# uSD.net
KiCad netlist of a schematic drawn in Altium Designer
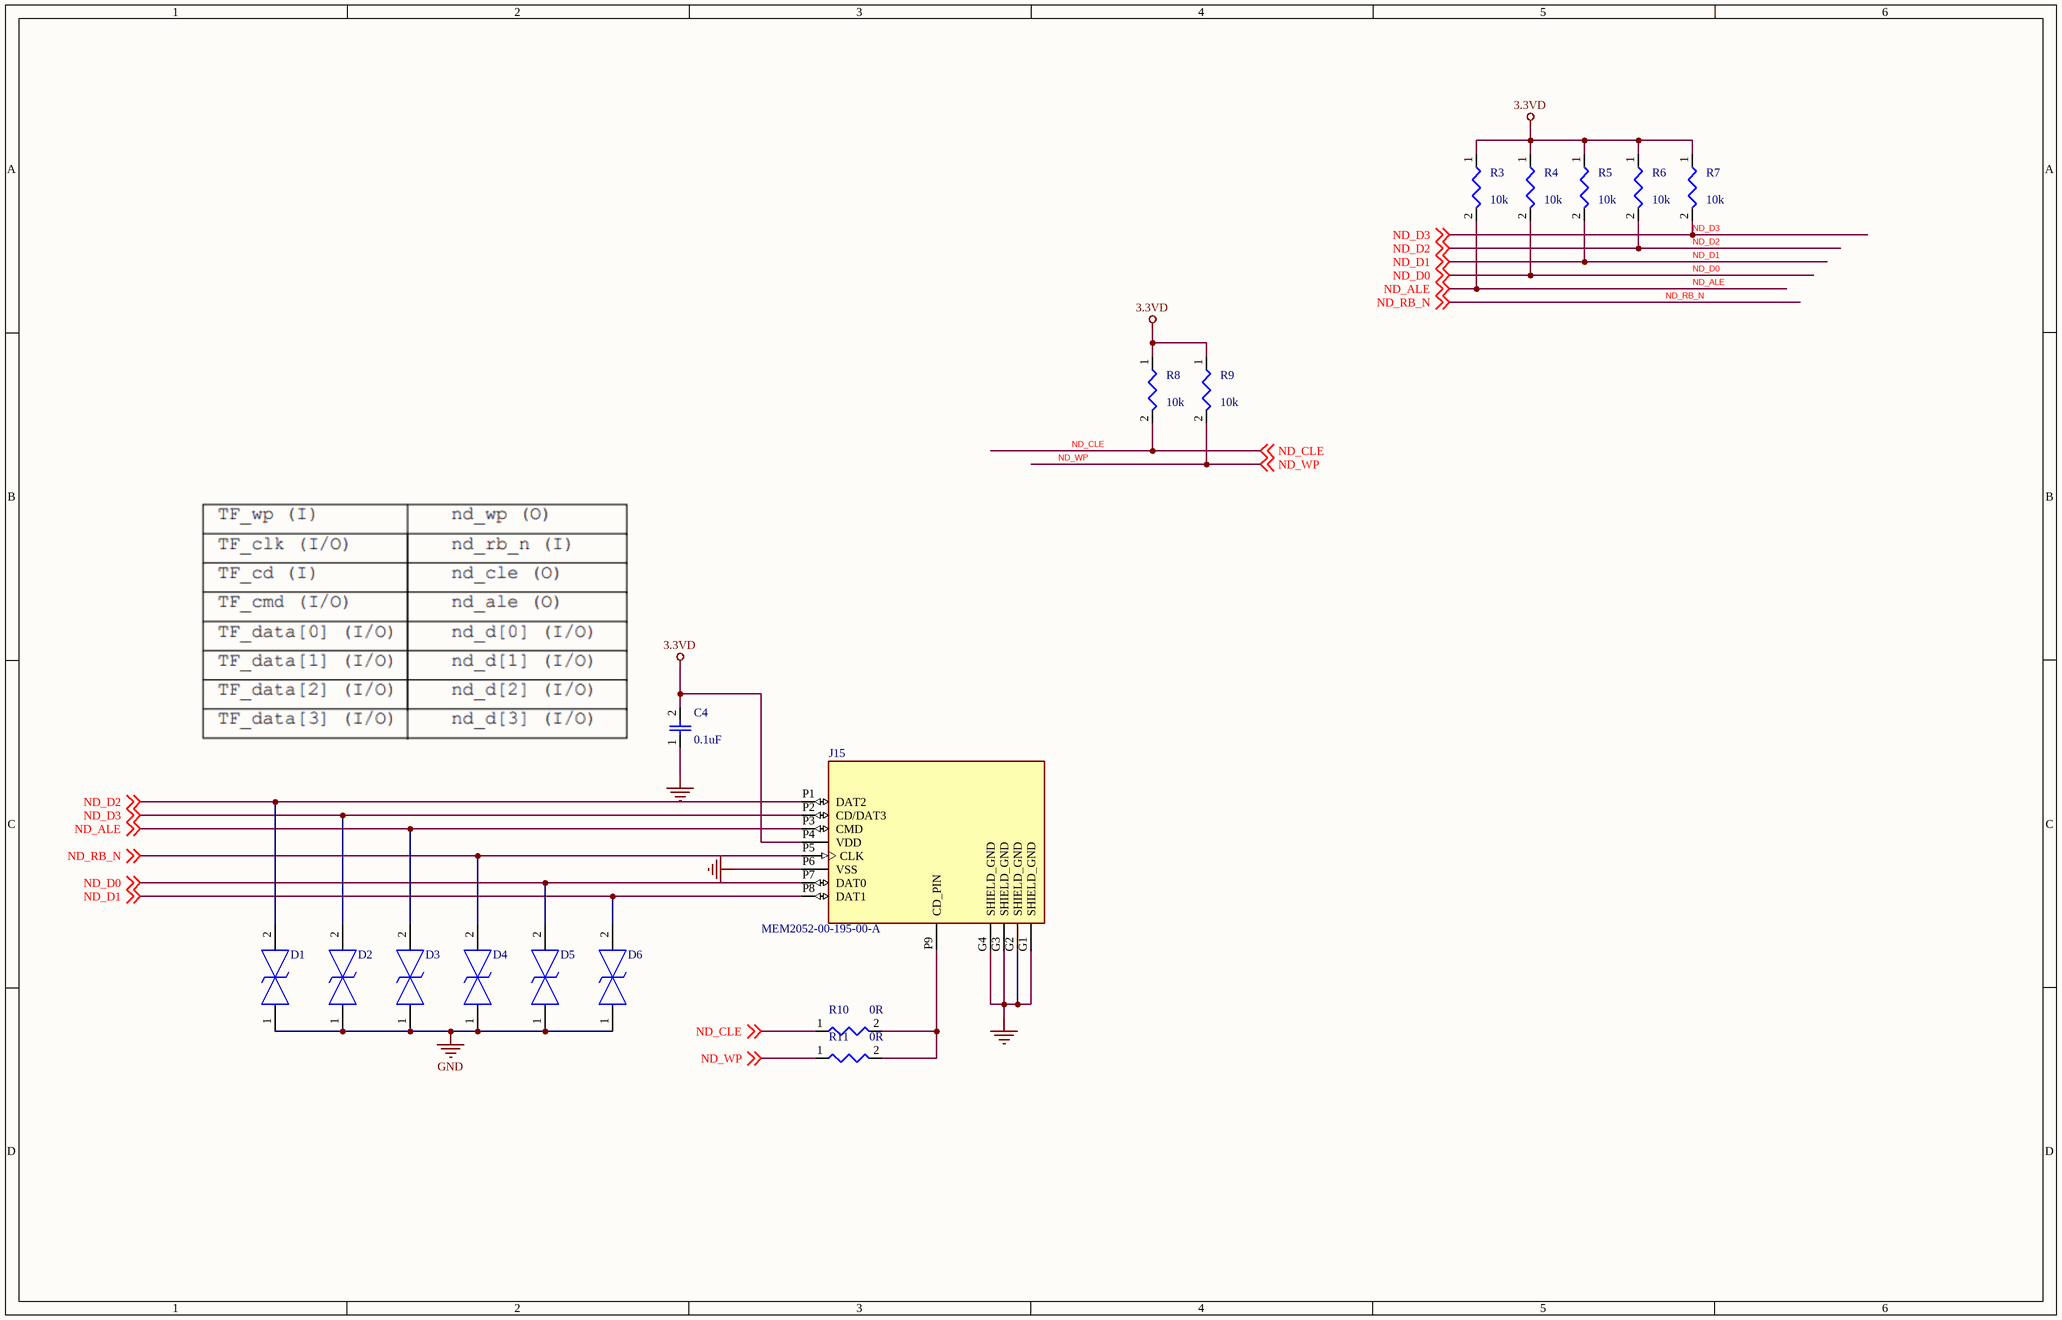
[diagram p0: uSD.SchDoc]

(export (version "E")
  (design (tool "Eeschema 10.0.6"))
  (components
    (comp (ref "C4") (value "0.1uF") (footprint "0402-C") (libsource (lib "OOLITEV8") (part "CAP")))
    (comp (ref "D1")
      (value "ESD9B5VL-2_TR")
      (footprint "SamacSys:ESD9B5VL2TR")
      (description "TVS Diode (Bi-directional)")
      (fields (field (name "MANUFACTURER_PART_NUMBER") "ESD9B5VL-2/TR"))
      (libsource (lib "*") (part "ESD9B5VL-2_TR"))
    )
    (comp (ref "D2")
      (value "ESD9B5VL-2_TR")
      (footprint "SamacSys:ESD9B5VL2TR")
      (description "TVS Diode (Bi-directional)")
      (fields (field (name "MANUFACTURER_PART_NUMBER") "ESD9B5VL-2/TR"))
      (libsource (lib "*") (part "ESD9B5VL-2_TR"))
    )
    (comp (ref "D3")
      (value "ESD9B5VL-2_TR")
      (footprint "SamacSys:ESD9B5VL2TR")
      (description "TVS Diode (Bi-directional)")
      (fields (field (name "MANUFACTURER_PART_NUMBER") "ESD9B5VL-2/TR"))
      (libsource (lib "*") (part "ESD9B5VL-2_TR"))
    )
    (comp (ref "D4")
      (value "ESD9B5VL-2_TR")
      (footprint "SamacSys:ESD9B5VL2TR")
      (description "TVS Diode (Bi-directional)")
      (fields (field (name "MANUFACTURER_PART_NUMBER") "ESD9B5VL-2/TR"))
      (libsource (lib "*") (part "ESD9B5VL-2_TR"))
    )
    (comp (ref "D5")
      (value "ESD9B5VL-2_TR")
      (footprint "SamacSys:ESD9B5VL2TR")
      (description "TVS Diode (Bi-directional)")
      (fields (field (name "MANUFACTURER_PART_NUMBER") "ESD9B5VL-2/TR"))
      (libsource (lib "*") (part "ESD9B5VL-2_TR"))
    )
    (comp (ref "D6")
      (value "ESD9B5VL-2_TR")
      (footprint "SamacSys:ESD9B5VL2TR")
      (description "TVS Diode (Bi-directional)")
      (fields (field (name "MANUFACTURER_PART_NUMBER") "ESD9B5VL-2/TR"))
      (libsource (lib "*") (part "ESD9B5VL-2_TR"))
    )
    (comp (ref "J15")
      (value "MEM2052-00-195-00-A")
      (footprint "GCT_MEM2052-00-195-00-A_REVA")
      (description "MicroSD Push push Memory Card Connector")
      (fields (field (name "MF") "Global Connector Technology"))
      (libsource (lib "MEM2052-00-195-00-A_REVA") (part "MEM2052-00-195-00-A_REVA"))
    )
    (comp (ref "R3") (value "10k") (footprint "0402-R") (libsource (lib "OOLITEV8") (part "Res")))
    (comp (ref "R4") (value "10k") (footprint "0402-R") (libsource (lib "OOLITEV8") (part "Res")))
    (comp (ref "R5") (value "10k") (footprint "0402-R") (libsource (lib "OOLITEV8") (part "Res")))
    (comp (ref "R6") (value "10k") (footprint "0402-R") (libsource (lib "OOLITEV8") (part "Res")))
    (comp (ref "R7") (value "10k") (footprint "0402-R") (libsource (lib "OOLITEV8") (part "Res")))
    (comp (ref "R8") (value "10k") (footprint "0402-R") (libsource (lib "OOLITEV8") (part "Res")))
    (comp (ref "R9") (value "10k") (footprint "0402-R") (libsource (lib "OOLITEV8") (part "Res")))
    (comp (ref "R10") (value "0R") (footprint "0402-R") (libsource (lib "OOLITEV8") (part "Res")))
    (comp (ref "R11") (value "0R") (footprint "0402-R") (libsource (lib "OOLITEV8") (part "Res")))
  )
  (nets
    (net (code "1") (name "3.3VD") (class "Default")
      (node (ref "C4") (pin "2") (pinfunction "2_2") (pintype "passive"))
      (node (ref "J15") (pin "P4") (pinfunction "VDD_P4") (pintype "power_in"))
      (node (ref "R3") (pin "1") (pinfunction "1_1") (pintype "passive"))
      (node (ref "R4") (pin "1") (pinfunction "1_1") (pintype "passive"))
      (node (ref "R5") (pin "1") (pinfunction "1_1") (pintype "passive"))
      (node (ref "R6") (pin "1") (pinfunction "1_1") (pintype "passive"))
      (node (ref "R7") (pin "1") (pinfunction "1_1") (pintype "passive"))
      (node (ref "R8") (pin "1") (pinfunction "1_1") (pintype "passive"))
      (node (ref "R9") (pin "1") (pinfunction "1_1") (pintype "passive"))
    )
    (net (code "2") (name "GND") (class "Default")
      (node (ref "C4") (pin "1") (pinfunction "1_1") (pintype "passive"))
      (node (ref "D1") (pin "1") (pinfunction "1_1") (pintype "passive"))
      (node (ref "D2") (pin "1") (pinfunction "1_1") (pintype "passive"))
      (node (ref "D3") (pin "1") (pinfunction "1_1") (pintype "passive"))
      (node (ref "D4") (pin "1") (pinfunction "1_1") (pintype "passive"))
      (node (ref "D5") (pin "1") (pinfunction "1_1") (pintype "passive"))
      (node (ref "D6") (pin "1") (pinfunction "1_1") (pintype "passive"))
      (node (ref "J15") (pin "G1") (pinfunction "SHIELD_GND_G1") (pintype "power_in"))
      (node (ref "J15") (pin "G2") (pinfunction "SHIELD_GND_G2") (pintype "power_in"))
      (node (ref "J15") (pin "G3") (pinfunction "SHIELD_GND_G3") (pintype "power_in"))
      (node (ref "J15") (pin "G4") (pinfunction "SHIELD_GND_G4") (pintype "power_in"))
      (node (ref "J15") (pin "P6") (pinfunction "VSS_P6") (pintype "power_in"))
    )
    (net (code "3") (name "ND_ALE") (class "Default")
      (node (ref "D3") (pin "2") (pinfunction "2_2") (pintype "passive"))
      (node (ref "J15") (pin "P3") (pinfunction "CMD_P3") (pintype "bidirectional"))
      (node (ref "R3") (pin "2") (pinfunction "2_2") (pintype "passive"))
    )
    (net (code "4") (name "ND_CLE") (class "Default")
      (node (ref "R10") (pin "1") (pinfunction "1_1") (pintype "passive"))
      (node (ref "R8") (pin "2") (pinfunction "2_2") (pintype "passive"))
    )
    (net (code "5") (name "ND_D0") (class "Default")
      (node (ref "D5") (pin "2") (pinfunction "2_2") (pintype "passive"))
      (node (ref "J15") (pin "P7") (pinfunction "DAT0_P7") (pintype "bidirectional"))
      (node (ref "R4") (pin "2") (pinfunction "2_2") (pintype "passive"))
    )
    (net (code "6") (name "ND_D1") (class "Default")
      (node (ref "D6") (pin "2") (pinfunction "2_2") (pintype "passive"))
      (node (ref "J15") (pin "P8") (pinfunction "DAT1_P8") (pintype "bidirectional"))
      (node (ref "R5") (pin "2") (pinfunction "2_2") (pintype "passive"))
    )
    (net (code "7") (name "ND_D2") (class "Default")
      (node (ref "D1") (pin "2") (pinfunction "2_2") (pintype "passive"))
      (node (ref "J15") (pin "P1") (pinfunction "DAT2_P1") (pintype "bidirectional"))
      (node (ref "R6") (pin "2") (pinfunction "2_2") (pintype "passive"))
    )
    (net (code "8") (name "ND_D3") (class "Default")
      (node (ref "D2") (pin "2") (pinfunction "2_2") (pintype "passive"))
      (node (ref "J15") (pin "P2") (pinfunction "CD/DAT3_P2") (pintype "bidirectional"))
      (node (ref "R7") (pin "2") (pinfunction "2_2") (pintype "passive"))
    )
    (net (code "9") (name "ND_RB_N") (class "Default")
      (node (ref "D4") (pin "2") (pinfunction "2_2") (pintype "passive"))
      (node (ref "J15") (pin "P5") (pinfunction "CLK_P5") (pintype "input"))
    )
    (net (code "10") (name "ND_WP") (class "Default")
      (node (ref "R11") (pin "1") (pinfunction "1_1") (pintype "passive"))
      (node (ref "R9") (pin "2") (pinfunction "2_2") (pintype "passive"))
    )
    (net (code "11") (name "Net-(J15-CD_PIN)") (class "Default")
      (node (ref "J15") (pin "P9") (pinfunction "CD_PIN_P9") (pintype "passive"))
      (node (ref "R10") (pin "2") (pinfunction "2_2") (pintype "passive"))
      (node (ref "R11") (pin "2") (pinfunction "2_2") (pintype "passive"))
    )
  )
)
